# LPCB223_-_BMS_INTERFACE.net
KiCad netlist of a schematic drawn in Altium Designer
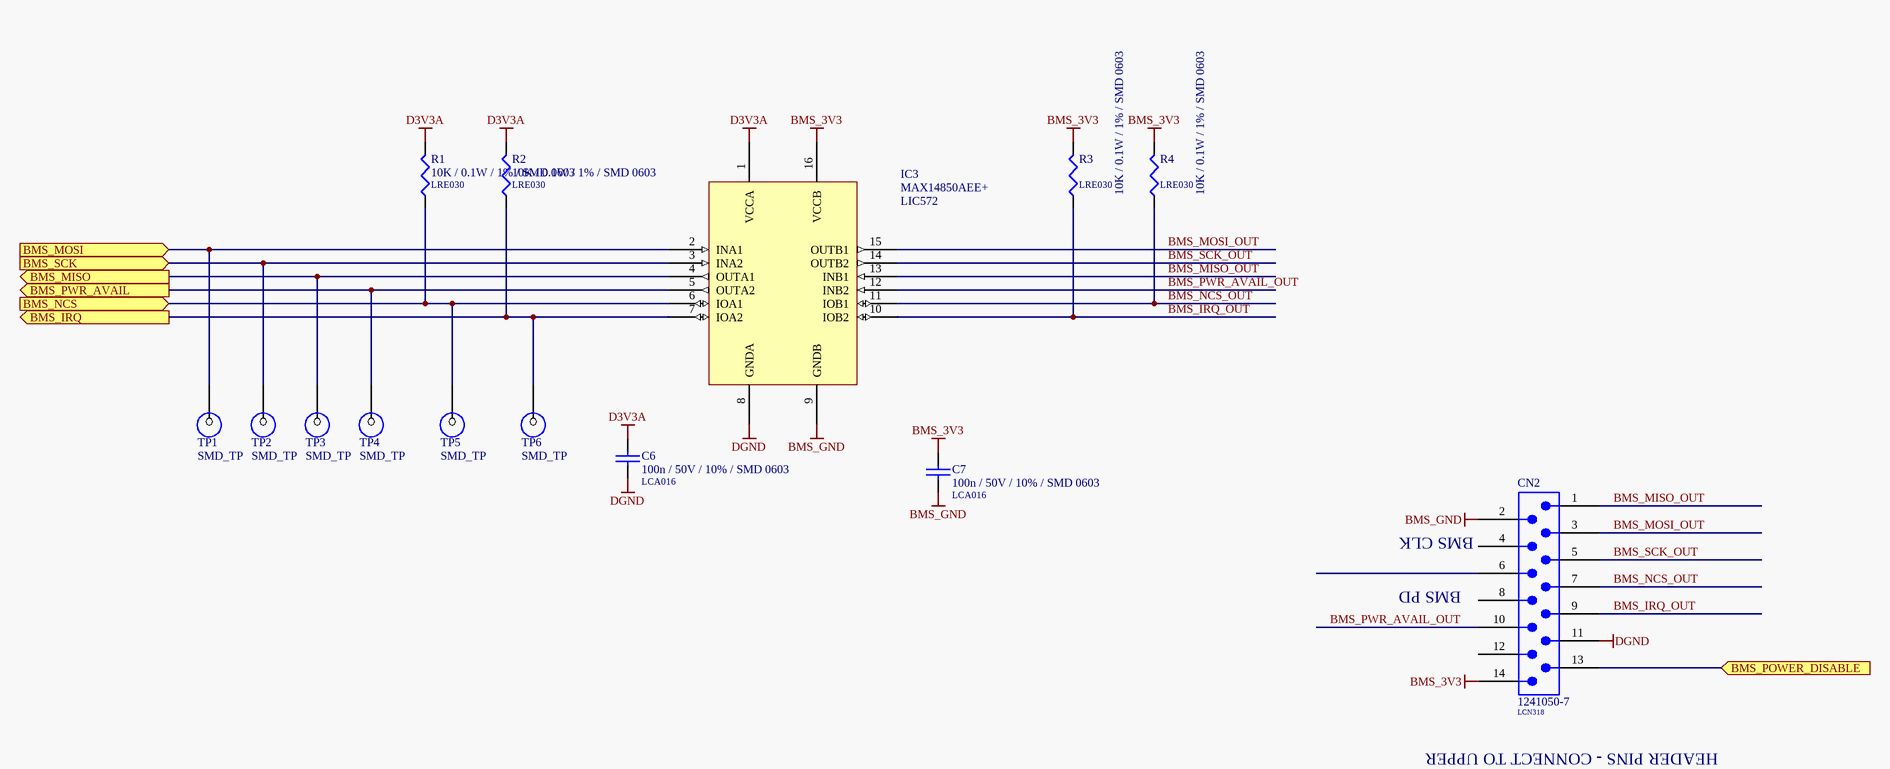
[diagram p0: LPCB223 - BMS INTERFACE.SchDoc]

(export (version "E")
  (design (tool "Eeschema 10.0.6"))
  (components
    (comp (ref "C6")
      (value "100n / 50V / 10% / SMD 0603")
      (footprint "LFP011__CC1608-0603-IPC7351_B")
      (description "Capacitor, Ceramic Chip, 100nF (0.1uF), 50V, 5%, SMD 0603 [LCA016]")
      (fields (field (name "LDL_NUMBER") "LCA016"))
      (libsource (lib "LDL_Capacitors") (part "100n / 50V / 10% / SMD 0603"))
    )
    (comp (ref "C7")
      (value "100n / 50V / 10% / SMD 0603")
      (footprint "LFP011__CC1608-0603-IPC7351_B")
      (description "Capacitor, Ceramic Chip, 100nF (0.1uF), 50V, 5%, SMD 0603 [LCA016]")
      (fields (field (name "LDL_NUMBER") "LCA016"))
      (libsource (lib "LDL_Capacitors") (part "100n / 50V / 10% / SMD 0603"))
    )
    (comp (ref "CN2")
      (value "1241050-7")
      (footprint "1241050-7")
      (description "Connector, Header, 2.54mm, 7 Pins x 2 Rows, SMD")
      (fields (field (name "LDL_NUMBER") "LCN318"))
      (libsource (lib "LDL_Connectors") (part "1241050-7"))
    )
    (comp (ref "IC3")
      (value "MAX14850AEE+")
      (footprint "LFP137__PW016")
      (description "IC, 6 Channel Digital Isolator, SMD [LIC572]")
      (fields (field (name "LDL_NUMBER") "LIC572"))
      (libsource (lib "LDL_Semiconductors") (part "MAX14850AEE+"))
    )
    (comp (ref "R1")
      (value "10K / 0.1W / 1% / SMD 0603")
      (footprint "LFP020__CR1608-0603-IPC7351_B")
      (description "Resistor, Ceramic Chip, 10K, 0.1W, 1%, SMD 0603 [LRE030]")
      (fields (field (name "LDL_NUMBER") "LRE030"))
      (libsource (lib "LDL_Resistors") (part "10K / 0.1W / 1% / SMD 0603"))
    )
    (comp (ref "R2")
      (value "10K / 0.1W / 1% / SMD 0603")
      (footprint "LFP020__CR1608-0603-IPC7351_B")
      (description "Resistor, Ceramic Chip, 10K, 0.1W, 1%, SMD 0603 [LRE030]")
      (fields (field (name "LDL_NUMBER") "LRE030"))
      (libsource (lib "LDL_Resistors") (part "10K / 0.1W / 1% / SMD 0603"))
    )
    (comp (ref "R3")
      (value "10K / 0.1W / 1% / SMD 0603")
      (footprint "LFP020__CR1608-0603-IPC7351_B")
      (description "Resistor, Ceramic Chip, 10K, 0.1W, 1%, SMD 0603 [LRE030]")
      (fields (field (name "LDL_NUMBER") "LRE030"))
      (libsource (lib "LDL_Resistors") (part "10K / 0.1W / 1% / SMD 0603"))
    )
    (comp (ref "R4")
      (value "10K / 0.1W / 1% / SMD 0603")
      (footprint "LFP020__CR1608-0603-IPC7351_B")
      (description "Resistor, Ceramic Chip, 10K, 0.1W, 1%, SMD 0603 [LRE030]")
      (fields (field (name "LDL_NUMBER") "LRE030"))
      (libsource (lib "LDL_Resistors") (part "10K / 0.1W / 1% / SMD 0603"))
    )
    (comp (ref "TP1")
      (value "SMD_TP")
      (footprint "SMD-TP")
      (description "SMD Test Point")
      (libsource (lib "LDL_Connectors") (part "SMD_TP"))
    )
    (comp (ref "TP2")
      (value "SMD_TP")
      (footprint "SMD-TP")
      (description "SMD Test Point")
      (libsource (lib "LDL_Connectors") (part "SMD_TP"))
    )
    (comp (ref "TP3")
      (value "SMD_TP")
      (footprint "SMD-TP")
      (description "SMD Test Point")
      (libsource (lib "LDL_Connectors") (part "SMD_TP"))
    )
    (comp (ref "TP4")
      (value "SMD_TP")
      (footprint "SMD-TP")
      (description "SMD Test Point")
      (libsource (lib "LDL_Connectors") (part "SMD_TP"))
    )
    (comp (ref "TP5")
      (value "SMD_TP")
      (footprint "SMD-TP")
      (description "SMD Test Point")
      (libsource (lib "LDL_Connectors") (part "SMD_TP"))
    )
    (comp (ref "TP6")
      (value "SMD_TP")
      (footprint "SMD-TP")
      (description "SMD Test Point")
      (libsource (lib "LDL_Connectors") (part "SMD_TP"))
    )
  )
  (nets
    (net (code "1") (name "/BMS_IRQ") (class "Default")
      (node (ref "IC3") (pin "7") (pinfunction "IOA2_7") (pintype "bidirectional"))
      (node (ref "R2") (pin "1") (pintype "passive"))
      (node (ref "TP6") (pin "1") (pintype "passive"))
    )
    (net (code "2") (name "/BMS_IRQ_OUT") (class "Default")
      (node (ref "CN2") (pin "9") (pinfunction "9_9") (pintype "passive"))
      (node (ref "IC3") (pin "10") (pinfunction "IOB2_10") (pintype "bidirectional"))
      (node (ref "R3") (pin "1") (pintype "passive"))
    )
    (net (code "3") (name "/BMS_MISO") (class "Default")
      (node (ref "IC3") (pin "4") (pinfunction "OUTA1_4") (pintype "output"))
      (node (ref "TP3") (pin "1") (pintype "passive"))
    )
    (net (code "4") (name "/BMS_MISO_OUT") (class "Default")
      (node (ref "CN2") (pin "1") (pinfunction "1_1") (pintype "passive"))
      (node (ref "IC3") (pin "13") (pinfunction "INB1_13") (pintype "input"))
    )
    (net (code "5") (name "/BMS_MOSI") (class "Default")
      (node (ref "IC3") (pin "2") (pinfunction "INA1_2") (pintype "input"))
      (node (ref "TP1") (pin "1") (pintype "passive"))
    )
    (net (code "6") (name "/BMS_MOSI_OUT") (class "Default")
      (node (ref "CN2") (pin "3") (pinfunction "3_3") (pintype "passive"))
      (node (ref "IC3") (pin "15") (pinfunction "OUTB1_15") (pintype "output"))
    )
    (net (code "7") (name "/BMS_NCS") (class "Default")
      (node (ref "IC3") (pin "6") (pinfunction "IOA1_6") (pintype "bidirectional"))
      (node (ref "R1") (pin "1") (pintype "passive"))
      (node (ref "TP5") (pin "1") (pintype "passive"))
    )
    (net (code "8") (name "/BMS_NCS_OUT") (class "Default")
      (node (ref "CN2") (pin "7") (pinfunction "7_7") (pintype "passive"))
      (node (ref "IC3") (pin "11") (pinfunction "IOB1_11") (pintype "bidirectional"))
      (node (ref "R4") (pin "1") (pintype "passive"))
    )
    (net (code "9") (name "/BMS_POWER_DISABLE") (class "Default")
      (node (ref "CN2") (pin "13") (pinfunction "13_13") (pintype "passive"))
    )
    (net (code "10") (name "/BMS_PWR_AVAIL") (class "Default")
      (node (ref "IC3") (pin "5") (pinfunction "OUTA2_5") (pintype "output"))
      (node (ref "TP4") (pin "1") (pintype "passive"))
    )
    (net (code "11") (name "/BMS_PWR_AVAIL_OUT") (class "Default")
      (node (ref "CN2") (pin "10") (pinfunction "10_10") (pintype "passive"))
      (node (ref "IC3") (pin "12") (pinfunction "INB2_12") (pintype "input"))
    )
    (net (code "12") (name "/BMS_SCK") (class "Default")
      (node (ref "IC3") (pin "3") (pinfunction "INA2_3") (pintype "input"))
      (node (ref "TP2") (pin "1") (pintype "passive"))
    )
    (net (code "13") (name "/BMS_SCK_OUT") (class "Default")
      (node (ref "CN2") (pin "5") (pinfunction "5_5") (pintype "passive"))
      (node (ref "IC3") (pin "14") (pinfunction "OUTB2_14") (pintype "output"))
    )
    (net (code "14") (name "BMS_3V3") (class "Default")
      (node (ref "C7") (pin "1") (pintype "passive"))
      (node (ref "CN2") (pin "14") (pinfunction "14_14") (pintype "passive"))
      (node (ref "IC3") (pin "16") (pinfunction "VCCB_16") (pintype "power_in"))
      (node (ref "R3") (pin "2") (pintype "passive"))
      (node (ref "R4") (pin "2") (pintype "passive"))
    )
    (net (code "15") (name "BMS_GND") (class "Default")
      (node (ref "C7") (pin "2") (pintype "passive"))
      (node (ref "CN2") (pin "2") (pinfunction "2_2") (pintype "passive"))
      (node (ref "IC3") (pin "9") (pinfunction "GNDB_9") (pintype "power_in"))
    )
    (net (code "16") (name "D3V3A") (class "Default")
      (node (ref "C6") (pin "1") (pintype "passive"))
      (node (ref "IC3") (pin "1") (pinfunction "VCCA_1") (pintype "power_in"))
      (node (ref "R1") (pin "2") (pintype "passive"))
      (node (ref "R2") (pin "2") (pintype "passive"))
    )
    (net (code "17") (name "DGND") (class "Default")
      (node (ref "C6") (pin "2") (pintype "passive"))
      (node (ref "CN2") (pin "11") (pinfunction "11_11") (pintype "passive"))
      (node (ref "IC3") (pin "8") (pinfunction "GNDA_8") (pintype "power_in"))
    )
    (net (code "18") (name "unconnected-(CN2-Pad4)") (class "Default")
      (node (ref "CN2") (pin "4") (pinfunction "4_4") (pintype "passive"))
    )
    (net (code "19") (name "unconnected-(CN2-Pad6)") (class "Default")
      (node (ref "CN2") (pin "6") (pinfunction "6_6") (pintype "passive"))
    )
    (net (code "20") (name "unconnected-(CN2-Pad8)") (class "Default")
      (node (ref "CN2") (pin "8") (pinfunction "8_8") (pintype "passive"))
    )
    (net (code "21") (name "unconnected-(CN2-Pad12)") (class "Default")
      (node (ref "CN2") (pin "12") (pinfunction "12_12") (pintype "passive"))
    )
  )
)
